# SAM_E54_Xplained_Pro_triple_input_power_.net
KiCad netlist of a schematic drawn in Altium Designer
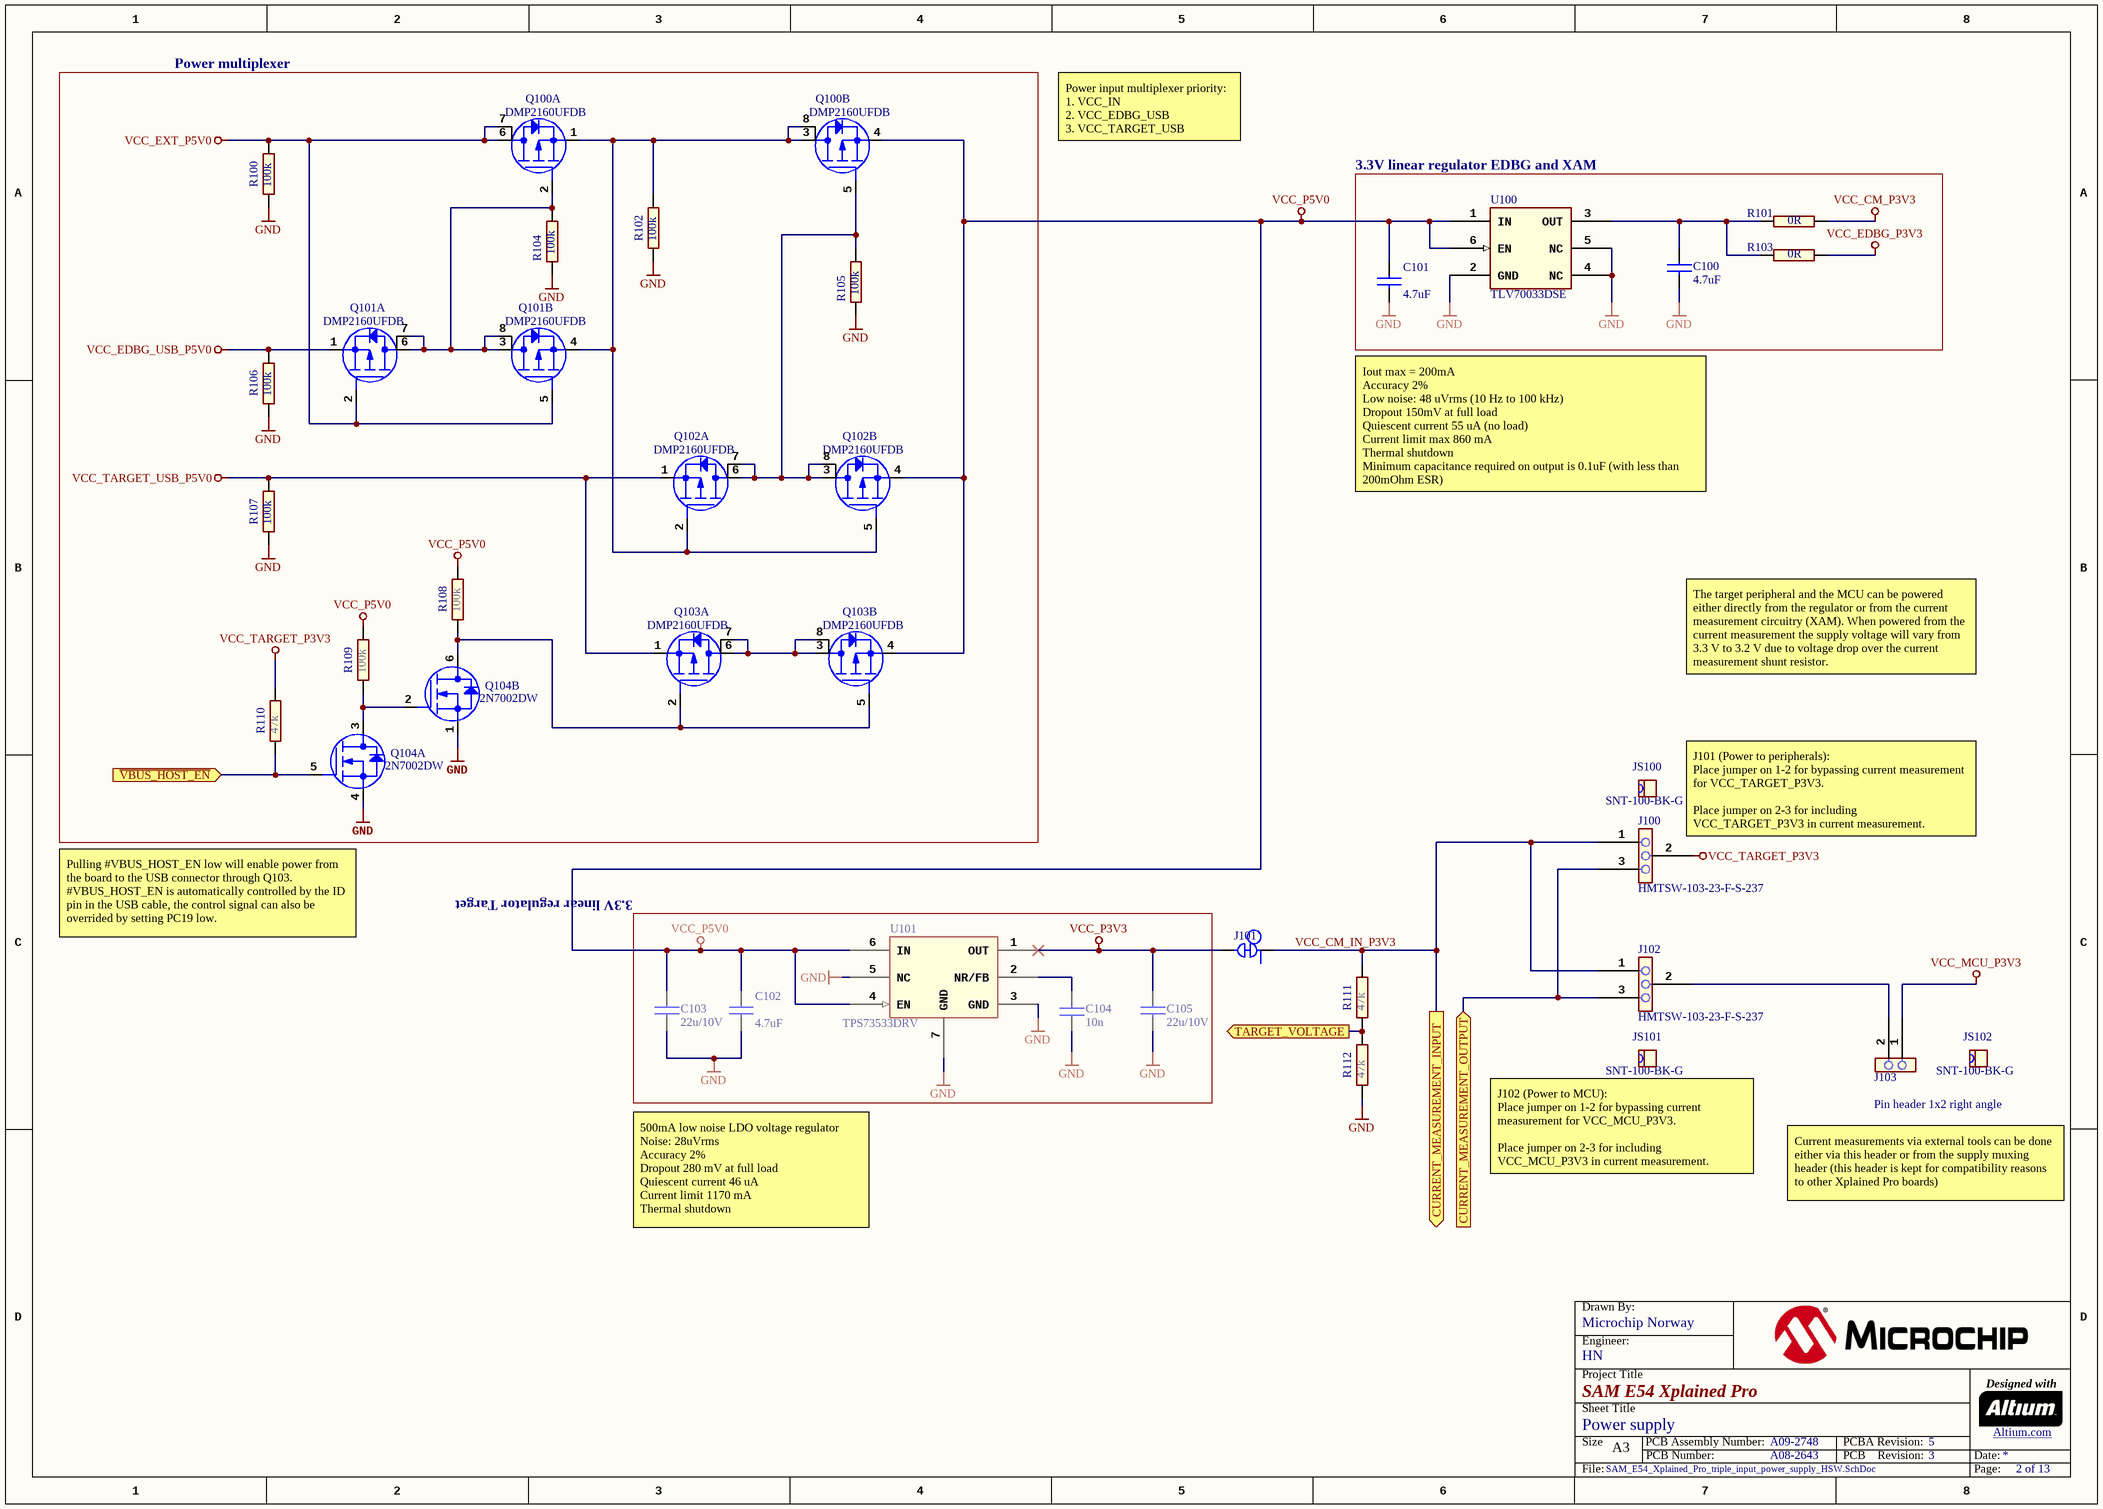
[diagram p0: SAM_E54_Xplained_Pro_triple_input_power_supply_HSW.SchDoc]

(export (version "E")
  (design (tool "Eeschema 10.0.6"))
  (components
    (comp (ref "C100")
      (value "4.7uF")
      (footprint "AP1-00117")
      (description "Ceramic capacitor, SMD 0603, X5R, 10V, 10% (de31036)")
      (fields (field (name "TOLERANCE") "10%") (field (name "MANUFACTURER") "WALSIN Technology Corporation"))
      (libsource (lib "AltiumDbLib") (part "CAP-NONPOL"))
    )
    (comp (ref "C101")
      (value "4.7uF")
      (footprint "AP1-00117")
      (description "Ceramic capacitor, SMD 0603, X5R, 10V, 10% (de31036)")
      (fields (field (name "TOLERANCE") "10%") (field (name "MANUFACTURER") "WALSIN Technology Corporation"))
      (libsource (lib "AltiumDbLib") (part "CAP-NONPOL"))
    )
    (comp (ref "C102")
      (value "4.7uF")
      (footprint "AP1-00117")
      (description "Ceramic capacitor, SMD 0603, X5R, 10V, 10% (de31036)")
      (fields (field (name "TOLERANCE") "10%") (field (name "MANUFACTURER") "WALSIN Technology Corporation"))
      (libsource (lib "AltiumDbLib") (part "CAP-NONPOL"))
    )
    (comp (ref "C103")
      (value "22u/10V")
      (footprint "AP1-00117")
      (description "Ceramic capacitor, SMD 0603, X5R,10V, Â±20%")
      (fields (field (name "MANUFACTURER") "Murata") (field (name "MPN") "GRM188R61A226ME15D"))
      (libsource (lib "AltiumDbLib") (part "CAP-NONPOL"))
    )
    (comp (ref "C104")
      (value "10n")
      (footprint "AP1-00053")
      (description "Ceramic capacitor, SMD 0402, X7R, 25V, +/-10%")
      (fields (field (name "TOLERANCE") "25V, +/-10%") (field (name "MANUFACTURER") "YAGEO CORP"))
      (libsource (lib "AltiumDbLib") (part "CAP-NONPOL"))
    )
    (comp (ref "C105")
      (value "22u/10V")
      (footprint "AP1-00117")
      (description "Ceramic capacitor, SMD 0603, X5R,10V, Â±20%")
      (fields (field (name "MANUFACTURER") "Murata") (field (name "MPN") "GRM188R61A226ME15D"))
      (libsource (lib "AltiumDbLib") (part "CAP-NONPOL"))
    )
    (comp (ref "J100")
      (value "HMTSW-103-23-F-S-237")
      (footprint "AP8-00745")
      (description "1x3 pin header, 2.54mm pitch, Pin-in-Paste THM, 1mm hole")
      (fields (field (name "MANUFACTURER") "SAMTEC"))
      (libsource (lib "AltiumDbLib") (part "HEADER 1x3"))
    )
    (comp (ref "J101")
      (value "~")
      (footprint "AP9-00044")
      (description "Default closed SMD strap, 0603 size")
      (libsource (lib "AltiumDbLib") (part "SMD-STRAP_CLOSED"))
    )
    (comp (ref "J102")
      (value "HMTSW-103-23-F-S-237")
      (footprint "AP8-00745")
      (description "1x3 pin header, 2.54mm pitch, Pin-in-Paste THM, 1mm hole")
      (fields (field (name "MANUFACTURER") "SAMTEC"))
      (libsource (lib "AltiumDbLib") (part "HEADER 1x3"))
    )
    (comp (ref "J103")
      (value "Pin header 1x2 right angle")
      (footprint "AP8-00367")
      (description "1x2 pin header, right angle, 2.54 mm pitch, through-hole")
      (fields (field (name "MANUFACTURER") "Pro-data International Corp") (field (name "MPN") "2213R-2G"))
      (libsource (lib "AltiumDbLib") (part "HEADER 1x2"))
    )
    (comp (ref "JS100")
      (value "SNT-100-BK-G")
      (footprint "AP8-00525")
      (description "Jumper cap for 2.54mm pinheader")
      (fields (field (name "MANUFACTURER") "SAMTEC"))
      (libsource (lib "AltiumDbLib") (part "JUMPER_CAP"))
    )
    (comp (ref "JS101")
      (value "SNT-100-BK-G")
      (footprint "AP8-00525")
      (description "Jumper cap for 2.54mm pinheader")
      (fields (field (name "MANUFACTURER") "SAMTEC"))
      (libsource (lib "AltiumDbLib") (part "JUMPER_CAP"))
    )
    (comp (ref "JS102")
      (value "SNT-100-BK-G")
      (footprint "AP8-00525")
      (description "Jumper cap for 2.54mm pinheader")
      (fields (field (name "MANUFACTURER") "SAMTEC"))
      (libsource (lib "AltiumDbLib") (part "JUMPER_CAP"))
    )
    (comp (ref "Q100")
      (value "DMP2160UFDB")
      (footprint "AP5-00047")
      (description "MOSFET 20V 3.8A DUAL P-CHAN, Rds 70 mOhms, Vgs 12V, Vds -20")
      (fields (field (name "MANUFACTURER") "Diodes Incorporated") (field (name "MPN") "DMP2160UFDB-7"))
      (libsource (lib "AltiumDbLib") (part "MOSFET_DUAL_P_S1G1D2S2G2D1D1D2"))
    )
    (comp (ref "Q101")
      (value "DMP2160UFDB")
      (footprint "AP5-00047")
      (description "MOSFET 20V 3.8A DUAL P-CHAN, Rds 70 mOhms, Vgs 12V, Vds -20")
      (fields (field (name "MANUFACTURER") "Diodes Incorporated") (field (name "MPN") "DMP2160UFDB-7"))
      (libsource (lib "AltiumDbLib") (part "MOSFET_DUAL_P_S1G1D2S2G2D1D1D2"))
    )
    (comp (ref "Q102")
      (value "DMP2160UFDB")
      (footprint "AP5-00047")
      (description "MOSFET 20V 3.8A DUAL P-CHAN, Rds 70 mOhms, Vgs 12V, Vds -20")
      (fields (field (name "MANUFACTURER") "Diodes Incorporated") (field (name "MPN") "DMP2160UFDB-7"))
      (libsource (lib "AltiumDbLib") (part "MOSFET_DUAL_P_S1G1D2S2G2D1D1D2"))
    )
    (comp (ref "Q103")
      (value "DMP2160UFDB")
      (footprint "AP5-00047")
      (description "MOSFET 20V 3.8A DUAL P-CHAN, Rds 70 mOhms, Vgs 12V, Vds -20")
      (fields (field (name "MANUFACTURER") "Diodes Incorporated") (field (name "MPN") "DMP2160UFDB-7"))
      (libsource (lib "AltiumDbLib") (part "MOSFET_DUAL_P_S1G1D2S2G2D1D1D2"))
    )
    (comp (ref "Q104")
      (value "2N7002DW")
      (footprint "AP5-00001")
      (description "Dual N-Channel MOSFET, 60V, 115mA cont,RDS(ON) < 7.5 Ohm @50mA@5V, SOT-363")
      (fields (field (name "MANUFACTURER") "Fairchild"))
      (libsource (lib "AltiumDbLib") (part "MOSFET_DUAL_N_S2G2D1S1G1D2"))
    )
    (comp (ref "R100")
      (value "100k")
      (footprint "AP2-00011")
      (description "Thick film resistor, SMD 0402, 1/16W, 1%")
      (fields (field (name "TOLERANCE") "1 %") (field (name "MANUFACTURER") "ASJ"))
      (libsource (lib "AltiumDbLib") (part "R2"))
    )
    (comp (ref "R101")
      (value "0R")
      (footprint "AP2-00011")
      (description "RES 0.0 OHM 1/16W 0402 SMD")
      (fields (field (name "TOLERANCE") "1 %") (field (name "MANUFACTURER") "(n/a)"))
      (libsource (lib "") (part "R2_2"))
    )
    (comp (ref "R102")
      (value "100k")
      (footprint "AP2-00011")
      (description "Thick film resistor, SMD 0402, 1/16W, 1%")
      (fields (field (name "TOLERANCE") "1 %") (field (name "MANUFACTURER") "ASJ"))
      (libsource (lib "AltiumDbLib") (part "R2"))
    )
    (comp (ref "R103")
      (value "0R")
      (footprint "AP2-00011")
      (description "RES 0.0 OHM 1/16W 0402 SMD")
      (fields (field (name "TOLERANCE") "1 %") (field (name "MANUFACTURER") "(n/a)"))
      (libsource (lib "") (part "R2_2"))
    )
    (comp (ref "R104")
      (value "100k")
      (footprint "AP2-00011")
      (description "Thick film resistor, SMD 0402, 1/16W, 1%")
      (fields (field (name "TOLERANCE") "1 %") (field (name "MANUFACTURER") "ASJ"))
      (libsource (lib "") (part "R2_1"))
    )
    (comp (ref "R105")
      (value "100k")
      (footprint "AP2-00011")
      (description "Thick film resistor, SMD 0402, 1/16W, 1%")
      (fields (field (name "TOLERANCE") "1 %") (field (name "MANUFACTURER") "ASJ"))
      (libsource (lib "AltiumDbLib") (part "R2"))
    )
    (comp (ref "R106")
      (value "100k")
      (footprint "AP2-00011")
      (description "Thick film resistor, SMD 0402, 1/16W, 1%")
      (fields (field (name "TOLERANCE") "1 %") (field (name "MANUFACTURER") "ASJ"))
      (libsource (lib "AltiumDbLib") (part "R2"))
    )
    (comp (ref "R107")
      (value "100k")
      (footprint "AP2-00011")
      (description "Thick film resistor, SMD 0402, 1/16W, 1%")
      (fields (field (name "TOLERANCE") "1 %") (field (name "MANUFACTURER") "ASJ"))
      (libsource (lib "AltiumDbLib") (part "R2"))
    )
    (comp (ref "R108")
      (value "100k")
      (footprint "AP2-00011")
      (description "Thick film resistor, SMD 0402, 1/16W, 1%")
      (fields (field (name "TOLERANCE") "1 %") (field (name "MANUFACTURER") "ASJ"))
      (libsource (lib "AltiumDbLib") (part "R2"))
    )
    (comp (ref "R109")
      (value "100k")
      (footprint "AP2-00011")
      (description "Thick film resistor, SMD 0402, 1/16W, 1%")
      (fields (field (name "TOLERANCE") "1 %") (field (name "MANUFACTURER") "ASJ"))
      (libsource (lib "AltiumDbLib") (part "R2"))
    )
    (comp (ref "R110")
      (value "47k")
      (footprint "AP2-00011")
      (description "Thick film resistor, SMD 0402, 1/16W, 1%")
      (fields (field (name "TOLERANCE") "1 %") (field (name "MANUFACTURER") "KOA"))
      (libsource (lib "") (part "R2_3"))
    )
    (comp (ref "R111")
      (value "47k")
      (footprint "AP2-00011")
      (description "Thick film resistor, SMD 0402, 1/16W, 1%")
      (fields (field (name "TOLERANCE") "1 %") (field (name "MANUFACTURER") "KOA"))
      (libsource (lib "") (part "R2_3"))
    )
    (comp (ref "R112")
      (value "47k")
      (footprint "AP2-00011")
      (description "Thick film resistor, SMD 0402, 1/16W, 1%")
      (fields (field (name "TOLERANCE") "1 %") (field (name "MANUFACTURER") "KOA"))
      (libsource (lib "") (part "R2_3"))
    )
    (comp (ref "U100")
      (value "TLV70033DSE")
      (footprint "AP6-00262")
      (description "LDO, 200 mA, Iq=31 uA, Vdo=250mV, Vout=3.3V, VIN= 2 V to 5.5V, SON-6 package")
      (fields (field (name "MANUFACTURER") "Texas Instruments"))
      (libsource (lib "AltiumDbLib") (part "TLV70033"))
    )
    (comp (ref "U101")
      (value "TPS73533DRV")
      (footprint "AP6-00162")
      (fields (field (name "MANUFACTURER") "Texas Instruments"))
      (libsource (lib "AltiumDbLib") (part "TPS735xxDRV"))
    )
  )
  (nets
    (net (code "1") (name "/CURRENT_MEASUREMENT_OUTPUT") (class "Default")
      (node (ref "J100") (pin "3") (pinfunction "3_3") (pintype "passive"))
      (node (ref "J102") (pin "3") (pinfunction "3_3") (pintype "passive"))
    )
    (net (code "2") (name "/TARGET_VOLTAGE") (class "Default")
      (node (ref "R111") (pin "1") (pinfunction "1_1") (pintype "passive"))
      (node (ref "R112") (pin "2") (pinfunction "2_2") (pintype "passive"))
    )
    (net (code "3") (name "/VCC_CM_IN_P3V3") (class "Default")
      (node (ref "J100") (pin "1") (pinfunction "1_1") (pintype "passive"))
      (node (ref "J101") (pin "1") (pinfunction "1_1") (pintype "passive"))
      (node (ref "J102") (pin "1") (pinfunction "1_1") (pintype "passive"))
      (node (ref "R111") (pin "2") (pinfunction "2_2") (pintype "passive"))
    )
    (net (code "4") (name "/~{VBUS_HOST_EN}") (class "Default")
      (node (ref "Q104") (pin "5") (pinfunction "G1_5") (pintype "passive"))
      (node (ref "R110") (pin "1") (pinfunction "1_1") (pintype "passive"))
    )
    (net (code "5") (name "GND") (class "Default")
      (node (ref "C100") (pin "2") (pinfunction "2_2") (pintype "passive"))
      (node (ref "C101") (pin "2") (pinfunction "2_2") (pintype "passive"))
      (node (ref "C102") (pin "2") (pinfunction "2_2") (pintype "passive"))
      (node (ref "C103") (pin "2") (pinfunction "2_2") (pintype "passive"))
      (node (ref "C104") (pin "1") (pinfunction "1_1") (pintype "passive"))
      (node (ref "C105") (pin "2") (pinfunction "2_2") (pintype "passive"))
      (node (ref "Q104") (pin "1") (pinfunction "S2_1") (pintype "passive"))
      (node (ref "Q104") (pin "4") (pinfunction "S1_4") (pintype "passive"))
      (node (ref "R100") (pin "1") (pinfunction "1_1") (pintype "passive"))
      (node (ref "R102") (pin "1") (pinfunction "1_1") (pintype "passive"))
      (node (ref "R104") (pin "2") (pinfunction "2_2") (pintype "passive"))
      (node (ref "R105") (pin "1") (pinfunction "1_1") (pintype "passive"))
      (node (ref "R106") (pin "1") (pinfunction "1_1") (pintype "passive"))
      (node (ref "R107") (pin "1") (pinfunction "1_1") (pintype "passive"))
      (node (ref "R112") (pin "1") (pinfunction "1_1") (pintype "passive"))
      (node (ref "U100") (pin "2") (pinfunction "GND_2") (pintype "power_in"))
      (node (ref "U100") (pin "4") (pinfunction "NC_4") (pintype "passive"))
      (node (ref "U100") (pin "5") (pinfunction "NC_5") (pintype "passive"))
      (node (ref "U101") (pin "3") (pinfunction "GND_3") (pintype "power_in"))
      (node (ref "U101") (pin "5") (pinfunction "NC_5") (pintype "passive"))
      (node (ref "U101") (pin "7") (pinfunction "GND_7") (pintype "power_in"))
    )
    (net (code "6") (name "Net-(J102-Pad2)") (class "Default")
      (node (ref "J102") (pin "2") (pinfunction "2_2") (pintype "passive"))
      (node (ref "J103") (pin "2") (pinfunction "2_2") (pintype "passive"))
    )
    (net (code "7") (name "Net-(Q100A-G1)") (class "Default")
      (node (ref "Q100") (pin "2") (pinfunction "G1_2") (pintype "passive"))
      (node (ref "Q101") (pin "3") (pinfunction "D2_3") (pintype "passive"))
      (node (ref "Q101") (pin "6") (pinfunction "D1_6") (pintype "passive"))
      (node (ref "Q101") (pin "7") (pinfunction "D1_PAD_7") (pintype "passive"))
      (node (ref "Q101") (pin "8") (pinfunction "D2_PAD_8") (pintype "passive"))
      (node (ref "R104") (pin "1") (pinfunction "1_1") (pintype "passive"))
    )
    (net (code "8") (name "Net-(Q100A-S1)") (class "Default")
      (node (ref "Q100") (pin "1") (pinfunction "S1_1") (pintype "passive"))
      (node (ref "Q100") (pin "3") (pinfunction "D2_3") (pintype "passive"))
      (node (ref "Q100") (pin "8") (pinfunction "D2_PAD_8") (pintype "passive"))
      (node (ref "Q101") (pin "4") (pinfunction "S2_4") (pintype "passive"))
      (node (ref "Q102") (pin "2") (pinfunction "G1_2") (pintype "passive"))
      (node (ref "Q102") (pin "5") (pinfunction "G2_5") (pintype "passive"))
      (node (ref "R102") (pin "2") (pinfunction "2_2") (pintype "passive"))
    )
    (net (code "9") (name "Net-(Q100B-G2)") (class "Default")
      (node (ref "Q100") (pin "5") (pinfunction "G2_5") (pintype "passive"))
      (node (ref "Q102") (pin "3") (pinfunction "D2_3") (pintype "passive"))
      (node (ref "Q102") (pin "6") (pinfunction "D1_6") (pintype "passive"))
      (node (ref "Q102") (pin "7") (pinfunction "D1_PAD_7") (pintype "passive"))
      (node (ref "Q102") (pin "8") (pinfunction "D2_PAD_8") (pintype "passive"))
      (node (ref "R105") (pin "2") (pinfunction "2_2") (pintype "passive"))
    )
    (net (code "10") (name "Net-(Q103A-D1)") (class "Default")
      (node (ref "Q103") (pin "3") (pinfunction "D2_3") (pintype "passive"))
      (node (ref "Q103") (pin "6") (pinfunction "D1_6") (pintype "passive"))
      (node (ref "Q103") (pin "7") (pinfunction "D1_PAD_7") (pintype "passive"))
      (node (ref "Q103") (pin "8") (pinfunction "D2_PAD_8") (pintype "passive"))
    )
    (net (code "11") (name "Net-(Q103A-G1)") (class "Default")
      (node (ref "Q103") (pin "2") (pinfunction "G1_2") (pintype "passive"))
      (node (ref "Q103") (pin "5") (pinfunction "G2_5") (pintype "passive"))
      (node (ref "Q104") (pin "6") (pinfunction "D2_6") (pintype "passive"))
      (node (ref "R108") (pin "1") (pinfunction "1_1") (pintype "passive"))
    )
    (net (code "12") (name "Net-(Q104A-D1)") (class "Default")
      (node (ref "Q104") (pin "2") (pinfunction "G2_2") (pintype "passive"))
      (node (ref "Q104") (pin "3") (pinfunction "D1_3") (pintype "passive"))
      (node (ref "R109") (pin "1") (pinfunction "1_1") (pintype "passive"))
    )
    (net (code "13") (name "Net-(U100-OUT)") (class "Default")
      (node (ref "C100") (pin "1") (pinfunction "1_1") (pintype "passive"))
      (node (ref "R101") (pin "2") (pinfunction "2_2") (pintype "passive"))
      (node (ref "R103") (pin "2") (pinfunction "2_2") (pintype "passive"))
      (node (ref "U100") (pin "3") (pinfunction "OUT_3") (pintype "power_in"))
    )
    (net (code "14") (name "Net-(U101-NR{slash}FB)") (class "Default")
      (node (ref "C104") (pin "2") (pinfunction "2_2") (pintype "passive"))
      (node (ref "U101") (pin "2") (pinfunction "NR/FB_2") (pintype "passive"))
    )
    (net (code "15") (name "VCC_CM_P3V3") (class "Default")
      (node (ref "R101") (pin "1") (pinfunction "1_1") (pintype "passive"))
    )
    (net (code "16") (name "VCC_EDBG_P3V3") (class "Default")
      (node (ref "R103") (pin "1") (pinfunction "1_1") (pintype "passive"))
    )
    (net (code "17") (name "VCC_EDBG_USB_P5V0") (class "Default")
      (node (ref "Q101") (pin "1") (pinfunction "S1_1") (pintype "passive"))
      (node (ref "R106") (pin "2") (pinfunction "2_2") (pintype "passive"))
    )
    (net (code "18") (name "VCC_EXT_P5V0") (class "Default")
      (node (ref "Q100") (pin "6") (pinfunction "D1_6") (pintype "passive"))
      (node (ref "Q100") (pin "7") (pinfunction "D1_PAD_7") (pintype "passive"))
      (node (ref "Q101") (pin "2") (pinfunction "G1_2") (pintype "passive"))
      (node (ref "Q101") (pin "5") (pinfunction "G2_5") (pintype "passive"))
      (node (ref "R100") (pin "2") (pinfunction "2_2") (pintype "passive"))
    )
    (net (code "19") (name "VCC_MCU_P3V3") (class "Default")
      (node (ref "J103") (pin "1") (pinfunction "1_1") (pintype "passive"))
    )
    (net (code "20") (name "VCC_P3V3") (class "Default")
      (node (ref "C105") (pin "1") (pinfunction "1_1") (pintype "passive"))
      (node (ref "J101") (pin "2") (pinfunction "2_2") (pintype "passive"))
      (node (ref "U101") (pin "1") (pinfunction "OUT_1") (pintype "power_in"))
    )
    (net (code "21") (name "VCC_P5V0") (class "Default")
      (node (ref "C101") (pin "1") (pinfunction "1_1") (pintype "passive"))
      (node (ref "C102") (pin "1") (pinfunction "1_1") (pintype "passive"))
      (node (ref "C103") (pin "1") (pinfunction "1_1") (pintype "passive"))
      (node (ref "Q100") (pin "4") (pinfunction "S2_4") (pintype "passive"))
      (node (ref "Q102") (pin "4") (pinfunction "S2_4") (pintype "passive"))
      (node (ref "Q103") (pin "4") (pinfunction "S2_4") (pintype "passive"))
      (node (ref "R108") (pin "2") (pinfunction "2_2") (pintype "passive"))
      (node (ref "R109") (pin "2") (pinfunction "2_2") (pintype "passive"))
      (node (ref "U100") (pin "1") (pinfunction "IN_1") (pintype "power_in"))
      (node (ref "U100") (pin "6") (pinfunction "EN_6") (pintype "input"))
      (node (ref "U101") (pin "4") (pinfunction "EN_4") (pintype "input"))
      (node (ref "U101") (pin "6") (pinfunction "IN_6") (pintype "power_in"))
    )
    (net (code "22") (name "VCC_TARGET_P3V3") (class "Default")
      (node (ref "J100") (pin "2") (pinfunction "2_2") (pintype "passive"))
      (node (ref "R110") (pin "2") (pinfunction "2_2") (pintype "passive"))
    )
    (net (code "23") (name "VCC_TARGET_USB_P5V0") (class "Default")
      (node (ref "Q102") (pin "1") (pinfunction "S1_1") (pintype "passive"))
      (node (ref "Q103") (pin "1") (pinfunction "S1_1") (pintype "passive"))
      (node (ref "R107") (pin "2") (pinfunction "2_2") (pintype "passive"))
    )
  )
)
